# Remote.net
KiCad netlist of a schematic drawn in Altium Designer
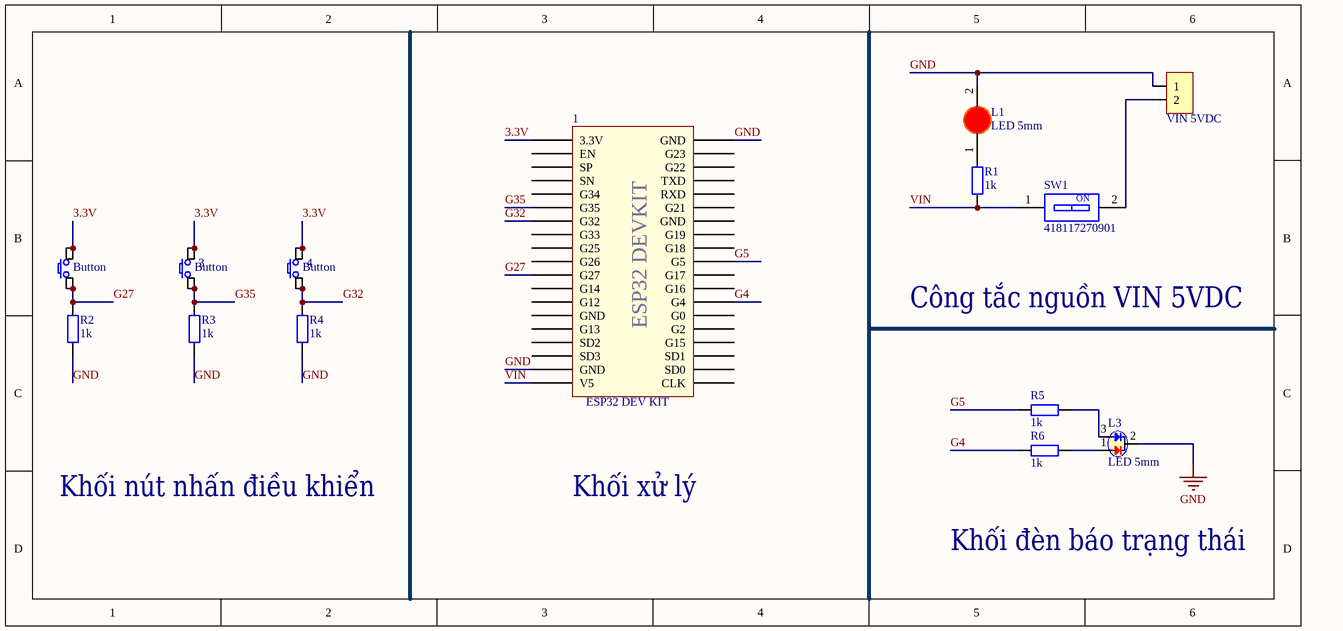
[diagram p0: Remote.SchDoc]

(export (version "E")
  (design (tool "Eeschema 10.0.6"))
  (components
    (comp (ref "1")
      (value "ESP32 DEV KIT")
      (footprint "ESP32 DEVKIT")
      (libsource (lib "Altium_Lib_by_KhueNguyenCreator") (part "ESP32 DEV KIT"))
    )
    (comp (ref "2")
      (value "Button")
      (footprint "SW/4/06MM")
      (description "Tact switch 4-pin")
      (libsource (lib "chipfc_altium_libs") (part "SW SPST 4-pin"))
    )
    (comp (ref "3")
      (value "Button")
      (footprint "SW/4/06MM")
      (description "Tact switch 4-pin")
      (libsource (lib "chipfc_altium_libs") (part "SW SPST 4-pin"))
    )
    (comp (ref "4")
      (value "Button")
      (footprint "SW/4/06MM")
      (description "Tact switch 4-pin")
      (libsource (lib "chipfc_altium_libs") (part "SW SPST 4-pin"))
    )
    (comp (ref "JP3")
      (value "VIN 5VDC")
      (footprint "JP 1x2 DT")
      (description "Cắm")
      (libsource (lib "Altium_Lib_by_KhueNguyenCreator") (part "JP 1x2 2.54 Duc Thang"))
    )
    (comp (ref "L1")
      (value "LED 5mm")
      (footprint "LED-5MM-RED")
      (description "Cắm")
      (libsource (lib "Altium_Lib_by_KhueNguyenCreator") (part "LED 5mm Do"))
    )
    (comp (ref "L3")
      (value "LED 5mm")
      (footprint "LED-5MM 2 MAU")
      (description "Cắm")
      (libsource (lib "Altium_Lib_by_KhueNguyenCreator") (part "LED 5mm 2 mau Katot chung"))
    )
    (comp (ref "R1")
      (value "1k")
      (footprint "tro vach 1/4w")
      (description "Cắm")
      (libsource (lib "Altium_Lib_by_KhueNguyenCreator") (part "Tro Vach 1/4W 5% 1k"))
    )
    (comp (ref "R2")
      (value "1k")
      (footprint "tro vach 1/4w")
      (description "Cắm")
      (libsource (lib "Altium_Lib_by_KhueNguyenCreator") (part "Tro Vach 1/4W 5% 1k"))
    )
    (comp (ref "R3")
      (value "1k")
      (footprint "tro vach 1/4w")
      (description "Cắm")
      (libsource (lib "Altium_Lib_by_KhueNguyenCreator") (part "Tro Vach 1/4W 5% 1k"))
    )
    (comp (ref "R4")
      (value "1k")
      (footprint "tro vach 1/4w")
      (description "Cắm")
      (libsource (lib "Altium_Lib_by_KhueNguyenCreator") (part "Tro Vach 1/4W 5% 1k"))
    )
    (comp (ref "R5")
      (value "1k")
      (footprint "tro vach 1/4w")
      (description "Cắm")
      (libsource (lib "Altium_Lib_by_KhueNguyenCreator") (part "Tro Vach 1/4W 5% 1k"))
    )
    (comp (ref "R6")
      (value "1k")
      (footprint "tro vach 1/4w")
      (description "Cắm")
      (libsource (lib "Altium_Lib_by_KhueNguyenCreator") (part "Tro Vach 1/4W 5% 1k"))
    )
    (comp (ref "SW1")
      (value "418117270901")
      (footprint "418117270901")
      (libsource (lib "Switch 1P DIP") (part "CMP-1435-00001-2"))
    )
  )
  (nets
    (net (code "1") (name "/3.3V") (class "Default")
      (node (ref "1") (pin "1") (pinfunction "3.3V_1") (pintype "passive"))
      (node (ref "2") (pin "3") (pinfunction "3_3") (pintype "passive"))
      (node (ref "2") (pin "4") (pinfunction "4_4") (pintype "passive"))
      (node (ref "3") (pin "3") (pinfunction "3_3") (pintype "passive"))
      (node (ref "3") (pin "4") (pinfunction "4_4") (pintype "passive"))
      (node (ref "4") (pin "3") (pinfunction "3_3") (pintype "passive"))
      (node (ref "4") (pin "4") (pinfunction "4_4") (pintype "passive"))
    )
    (net (code "2") (name "/G4") (class "Default")
      (node (ref "1") (pin "26") (pinfunction "G4_26") (pintype "passive"))
      (node (ref "R6") (pin "2") (pinfunction "2_2") (pintype "passive"))
    )
    (net (code "3") (name "/G5") (class "Default")
      (node (ref "1") (pin "29") (pinfunction "G5_29") (pintype "passive"))
      (node (ref "R5") (pin "2") (pinfunction "2_2") (pintype "passive"))
    )
    (net (code "4") (name "/G27") (class "Default")
      (node (ref "1") (pin "11") (pinfunction "G27_11") (pintype "passive"))
      (node (ref "2") (pin "1") (pinfunction "1_1") (pintype "passive"))
      (node (ref "2") (pin "2") (pinfunction "2_2") (pintype "passive"))
      (node (ref "R2") (pin "2") (pinfunction "2_2") (pintype "passive"))
    )
    (net (code "5") (name "/G32") (class "Default")
      (node (ref "1") (pin "7") (pinfunction "G32_7") (pintype "passive"))
      (node (ref "4") (pin "1") (pinfunction "1_1") (pintype "passive"))
      (node (ref "4") (pin "2") (pinfunction "2_2") (pintype "passive"))
      (node (ref "R4") (pin "2") (pinfunction "2_2") (pintype "passive"))
    )
    (net (code "6") (name "/G35") (class "Default")
      (node (ref "1") (pin "6") (pinfunction "G35_6") (pintype "passive"))
      (node (ref "3") (pin "1") (pinfunction "1_1") (pintype "passive"))
      (node (ref "3") (pin "2") (pinfunction "2_2") (pintype "passive"))
      (node (ref "R3") (pin "2") (pinfunction "2_2") (pintype "passive"))
    )
    (net (code "7") (name "/VIN") (class "Default")
      (node (ref "1") (pin "19") (pinfunction "V5_19") (pintype "passive"))
      (node (ref "R1") (pin "1") (pinfunction "1_1") (pintype "passive"))
      (node (ref "SW1") (pin "1") (pinfunction "1_1") (pintype "passive"))
    )
    (net (code "8") (name "GND") (class "Default")
      (node (ref "1") (pin "18") (pinfunction "GND_18") (pintype "passive"))
      (node (ref "1") (pin "38") (pinfunction "GND_38") (pintype "passive"))
      (node (ref "JP3") (pin "1") (pinfunction "1_1") (pintype "passive"))
      (node (ref "L1") (pin "2") (pinfunction "K_2") (pintype "passive"))
      (node (ref "L3") (pin "2") (pinfunction "Katot_2") (pintype "passive"))
      (node (ref "R2") (pin "1") (pinfunction "1_1") (pintype "passive"))
      (node (ref "R3") (pin "1") (pinfunction "1_1") (pintype "passive"))
      (node (ref "R4") (pin "1") (pinfunction "1_1") (pintype "passive"))
    )
    (net (code "9") (name "Net-(JP3-Pad2)") (class "Default")
      (node (ref "JP3") (pin "2") (pinfunction "2_2") (pintype "passive"))
      (node (ref "SW1") (pin "2") (pinfunction "2_2") (pintype "passive"))
    )
    (net (code "10") (name "Net-(L1-A)") (class "Default")
      (node (ref "L1") (pin "1") (pinfunction "A_1") (pintype "passive"))
      (node (ref "R1") (pin "2") (pinfunction "2_2") (pintype "passive"))
    )
    (net (code "11") (name "Net-(L3-D)") (class "Default")
      (node (ref "L3") (pin "1") (pinfunction "D_1") (pintype "passive"))
      (node (ref "R6") (pin "1") (pinfunction "1_1") (pintype "passive"))
    )
    (net (code "12") (name "Net-(L3-X)") (class "Default")
      (node (ref "L3") (pin "3") (pinfunction "X_3") (pintype "passive"))
      (node (ref "R5") (pin "1") (pinfunction "1_1") (pintype "passive"))
    )
    (net (code "13") (name "unconnected-(1-CLK-Pad20)") (class "Default")
      (node (ref "1") (pin "20") (pinfunction "CLK_20") (pintype "passive"))
    )
    (net (code "14") (name "unconnected-(1-EN-Pad2)") (class "Default")
      (node (ref "1") (pin "2") (pinfunction "EN_2") (pintype "passive"))
    )
    (net (code "15") (name "unconnected-(1-G0-Pad25)") (class "Default")
      (node (ref "1") (pin "25") (pinfunction "G0_25") (pintype "passive"))
    )
    (net (code "16") (name "unconnected-(1-G2-Pad24)") (class "Default")
      (node (ref "1") (pin "24") (pinfunction "G2_24") (pintype "passive"))
    )
    (net (code "17") (name "unconnected-(1-G12-Pad13)") (class "Default")
      (node (ref "1") (pin "13") (pinfunction "G12_13") (pintype "passive"))
    )
    (net (code "18") (name "unconnected-(1-G13-Pad15)") (class "Default")
      (node (ref "1") (pin "15") (pinfunction "G13_15") (pintype "passive"))
    )
    (net (code "19") (name "unconnected-(1-G14-Pad12)") (class "Default")
      (node (ref "1") (pin "12") (pinfunction "G14_12") (pintype "passive"))
    )
    (net (code "20") (name "unconnected-(1-G15-Pad23)") (class "Default")
      (node (ref "1") (pin "23") (pinfunction "G15_23") (pintype "passive"))
    )
    (net (code "21") (name "unconnected-(1-G16-Pad27)") (class "Default")
      (node (ref "1") (pin "27") (pinfunction "G16_27") (pintype "passive"))
    )
    (net (code "22") (name "unconnected-(1-G17-Pad28)") (class "Default")
      (node (ref "1") (pin "28") (pinfunction "G17_28") (pintype "passive"))
    )
    (net (code "23") (name "unconnected-(1-G18-Pad30)") (class "Default")
      (node (ref "1") (pin "30") (pinfunction "G18_30") (pintype "passive"))
    )
    (net (code "24") (name "unconnected-(1-G19-Pad31)") (class "Default")
      (node (ref "1") (pin "31") (pinfunction "G19_31") (pintype "passive"))
    )
    (net (code "25") (name "unconnected-(1-G21-Pad33)") (class "Default")
      (node (ref "1") (pin "33") (pinfunction "G21_33") (pintype "passive"))
    )
    (net (code "26") (name "unconnected-(1-G22-Pad36)") (class "Default")
      (node (ref "1") (pin "36") (pinfunction "G22_36") (pintype "passive"))
    )
    (net (code "27") (name "unconnected-(1-G23-Pad37)") (class "Default")
      (node (ref "1") (pin "37") (pinfunction "G23_37") (pintype "passive"))
    )
    (net (code "28") (name "unconnected-(1-G25-Pad9)") (class "Default")
      (node (ref "1") (pin "9") (pinfunction "G25_9") (pintype "passive"))
    )
    (net (code "29") (name "unconnected-(1-G26-Pad10)") (class "Default")
      (node (ref "1") (pin "10") (pinfunction "G26_10") (pintype "passive"))
    )
    (net (code "30") (name "unconnected-(1-G33-Pad8)") (class "Default")
      (node (ref "1") (pin "8") (pinfunction "G33_8") (pintype "passive"))
    )
    (net (code "31") (name "unconnected-(1-G34-Pad5)") (class "Default")
      (node (ref "1") (pin "5") (pinfunction "G34_5") (pintype "passive"))
    )
    (net (code "32") (name "unconnected-(1-GND-Pad14)") (class "Default")
      (node (ref "1") (pin "14") (pinfunction "GND_14") (pintype "passive"))
    )
    (net (code "33") (name "unconnected-(1-GND-Pad32)") (class "Default")
      (node (ref "1") (pin "32") (pinfunction "GND_32") (pintype "passive"))
    )
    (net (code "34") (name "unconnected-(1-RXD-Pad34)") (class "Default")
      (node (ref "1") (pin "34") (pinfunction "RXD_34") (pintype "passive"))
    )
    (net (code "35") (name "unconnected-(1-SD0-Pad21)") (class "Default")
      (node (ref "1") (pin "21") (pinfunction "SD0_21") (pintype "passive"))
    )
    (net (code "36") (name "unconnected-(1-SD1-Pad22)") (class "Default")
      (node (ref "1") (pin "22") (pinfunction "SD1_22") (pintype "passive"))
    )
    (net (code "37") (name "unconnected-(1-SD2-Pad16)") (class "Default")
      (node (ref "1") (pin "16") (pinfunction "SD2_16") (pintype "passive"))
    )
    (net (code "38") (name "unconnected-(1-SD3-Pad17)") (class "Default")
      (node (ref "1") (pin "17") (pinfunction "SD3_17") (pintype "passive"))
    )
    (net (code "39") (name "unconnected-(1-SN-Pad4)") (class "Default")
      (node (ref "1") (pin "4") (pinfunction "SN_4") (pintype "passive"))
    )
    (net (code "40") (name "unconnected-(1-SP-Pad3)") (class "Default")
      (node (ref "1") (pin "3") (pinfunction "SP_3") (pintype "passive"))
    )
    (net (code "41") (name "unconnected-(1-TXD-Pad35)") (class "Default")
      (node (ref "1") (pin "35") (pinfunction "TXD_35") (pintype "passive"))
    )
  )
)
